# Digital_Temperature_Sensor_Breakout_-_TM.net
KiCad netlist of a schematic drawn in EAGLE
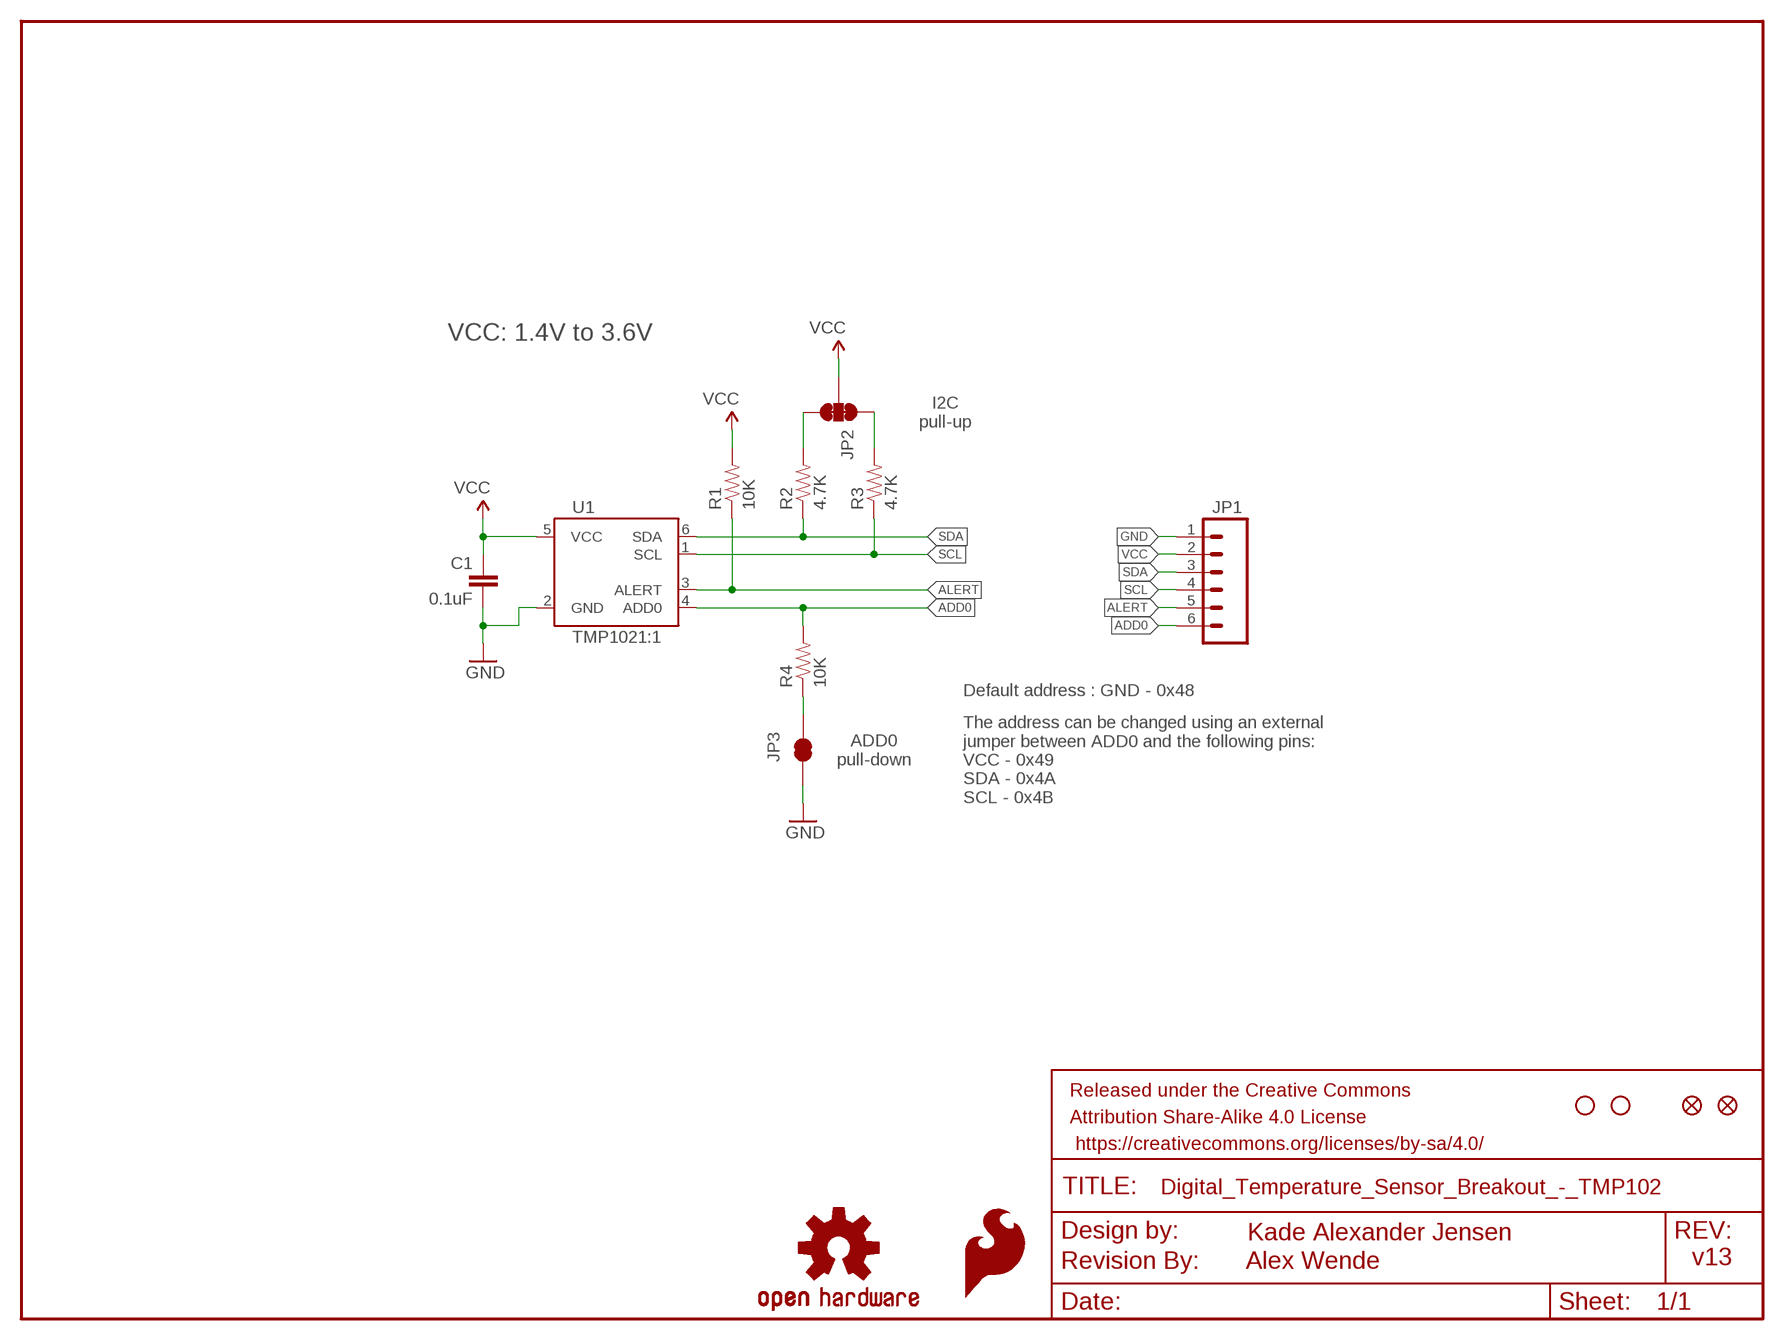
[diagram p0: schematic, sheet 1]

(export (version "E")
  (design (tool "Eeschema 10.0.6"))
  (components
    (comp (ref "C1")
      (value "0.1uF")
      (footprint "eagle-import:0603-CAP")
      (libsource (lib "eagle-import") (part "0.1UF-25V(+80/-20%)(0603)"))
    )
    (comp (ref "FRAME2")
      (value "FRAME-LETTER")
      (footprint "eagle-import:CREATIVE_COMMONS")
      (libsource (lib "eagle-import") (part "FRAME-LETTER"))
    )
    (comp (ref "JP1")
      (value "M06SIP")
      (footprint "eagle-import:1X06")
      (libsource (lib "eagle-import") (part "M06SIP"))
    )
    (comp (ref "JP2")
      (value "JUMPER-PAD-3-NC_BY_TRACE")
      (footprint "eagle-import:PAD-JUMPER-3-3OF3_NC_BY_TRACE_YES_SILK_FULL_BOX")
      (libsource (lib "eagle-import") (part "JUMPER-PAD-3-NC_BY_TRACE"))
    )
    (comp (ref "JP3")
      (value "ADD0")
      (footprint "eagle-import:PAD-JUMPER-2-NC_BY_TRACE_YES_SILK")
      (libsource (lib "eagle-import") (part "JUMPER-PAD-2-NC_BY_TRACE"))
    )
    (comp (ref "JP5")
      (value "FIDUCIAL1X2")
      (footprint "eagle-import:FIDUCIAL-1X2")
      (libsource (lib "eagle-import") (part "FIDUCIAL1X2"))
    )
    (comp (ref "JP6")
      (value "FIDUCIAL1X2")
      (footprint "eagle-import:FIDUCIAL-1X2")
      (libsource (lib "eagle-import") (part "FIDUCIAL1X2"))
    )
    (comp (ref "JP7")
      (value "STAND-OFFTIGHT")
      (footprint "eagle-import:STAND-OFF-TIGHT")
      (libsource (lib "eagle-import") (part "STAND-OFFTIGHT"))
    )
    (comp (ref "JP8")
      (value "STAND-OFFTIGHT")
      (footprint "eagle-import:STAND-OFF-TIGHT")
      (libsource (lib "eagle-import") (part "STAND-OFFTIGHT"))
    )
    (comp (ref "LOGO2")
      (value "SFE_LOGO_FLAME.1_INCH")
      (footprint "eagle-import:SFE_LOGO_FLAME_.1")
      (libsource (lib "eagle-import") (part "SFE_LOGO_FLAME.1_INCH"))
    )
    (comp (ref "LOGO3")
      (value "OSHW-LOGOS")
      (footprint "eagle-import:OSHW-LOGO-S")
      (libsource (lib "eagle-import") (part "OSHW-LOGOS"))
    )
    (comp (ref "R1")
      (value "10K")
      (footprint "eagle-import:0603-RES")
      (libsource (lib "eagle-import") (part "10KOHM-1/10W-1%(0603)0603"))
    )
    (comp (ref "R2")
      (value "4.7K")
      (footprint "eagle-import:0603-RES")
      (libsource (lib "eagle-import") (part "4.7KOHM-1/10W-1%(0603)"))
    )
    (comp (ref "R3")
      (value "4.7K")
      (footprint "eagle-import:0603-RES")
      (libsource (lib "eagle-import") (part "4.7KOHM-1/10W-1%(0603)"))
    )
    (comp (ref "R4")
      (value "10K")
      (footprint "eagle-import:0603-RES")
      (libsource (lib "eagle-import") (part "10KOHM-1/10W-1%(0603)0603"))
    )
    (comp (ref "U$2")
      (value "REVISION")
      (footprint "eagle-import:REVISION")
      (libsource (lib "eagle-import") (part "REVISION"))
    )
    (comp (ref "U1")
      (value "TMP1021:1")
      (footprint "eagle-import:SOT563-2")
      (libsource (lib "eagle-import") (part "TMP1021{colon}1"))
    )
  )
  (nets
    (net (code "1") (name "ADD0") (class "Default")
      (node (ref "JP1") (pin "6") (pinfunction "6_6") (pintype "passive"))
      (node (ref "R4") (pin "2") (pinfunction "2_2") (pintype "passive"))
      (node (ref "U1") (pin "4") (pinfunction "ADD0_4") (pintype "bidirectional"))
    )
    (net (code "2") (name "ALERT") (class "Default")
      (node (ref "JP1") (pin "5") (pinfunction "5_5") (pintype "passive"))
      (node (ref "R1") (pin "1") (pinfunction "1_1") (pintype "passive"))
      (node (ref "U1") (pin "3") (pinfunction "ALERT_3") (pintype "bidirectional"))
    )
    (net (code "3") (name "GND") (class "Default")
      (node (ref "C1") (pin "2") (pinfunction "2_2") (pintype "passive"))
      (node (ref "JP1") (pin "1") (pinfunction "1_1") (pintype "passive"))
      (node (ref "JP3") (pin "2") (pinfunction "2_2") (pintype "passive"))
      (node (ref "U1") (pin "2") (pinfunction "GND_2") (pintype "bidirectional"))
    )
    (net (code "4") (name "Net-(JP2-Pad1)") (class "Default")
      (node (ref "JP2") (pin "1") (pinfunction "1_1") (pintype "passive"))
      (node (ref "R3") (pin "2") (pinfunction "2_2") (pintype "passive"))
    )
    (net (code "5") (name "Net-(JP2-Pad3)") (class "Default")
      (node (ref "JP2") (pin "3") (pinfunction "3_3") (pintype "passive"))
      (node (ref "R2") (pin "2") (pinfunction "2_2") (pintype "passive"))
    )
    (net (code "6") (name "Net-(JP3-Pad1)") (class "Default")
      (node (ref "JP3") (pin "1") (pinfunction "1_1") (pintype "passive"))
      (node (ref "R4") (pin "1") (pinfunction "1_1") (pintype "passive"))
    )
    (net (code "7") (name "SCL") (class "Default")
      (node (ref "JP1") (pin "4") (pinfunction "4_4") (pintype "passive"))
      (node (ref "R3") (pin "1") (pinfunction "1_1") (pintype "passive"))
      (node (ref "U1") (pin "1") (pinfunction "SCL_1") (pintype "bidirectional"))
    )
    (net (code "8") (name "SDA") (class "Default")
      (node (ref "JP1") (pin "3") (pinfunction "3_3") (pintype "passive"))
      (node (ref "R2") (pin "1") (pinfunction "1_1") (pintype "passive"))
      (node (ref "U1") (pin "6") (pinfunction "SDA_6") (pintype "bidirectional"))
    )
    (net (code "9") (name "VCC") (class "Default")
      (node (ref "C1") (pin "1") (pinfunction "1_1") (pintype "passive"))
      (node (ref "JP1") (pin "2") (pinfunction "2_2") (pintype "passive"))
      (node (ref "JP2") (pin "2") (pinfunction "2_2") (pintype "passive"))
      (node (ref "R1") (pin "2") (pinfunction "2_2") (pintype "passive"))
      (node (ref "U1") (pin "5") (pinfunction "VCC_5") (pintype "bidirectional"))
    )
  )
)
